# Data_Logger_Shield_V2.net
KiCad netlist of a schematic drawn in Altium Designer
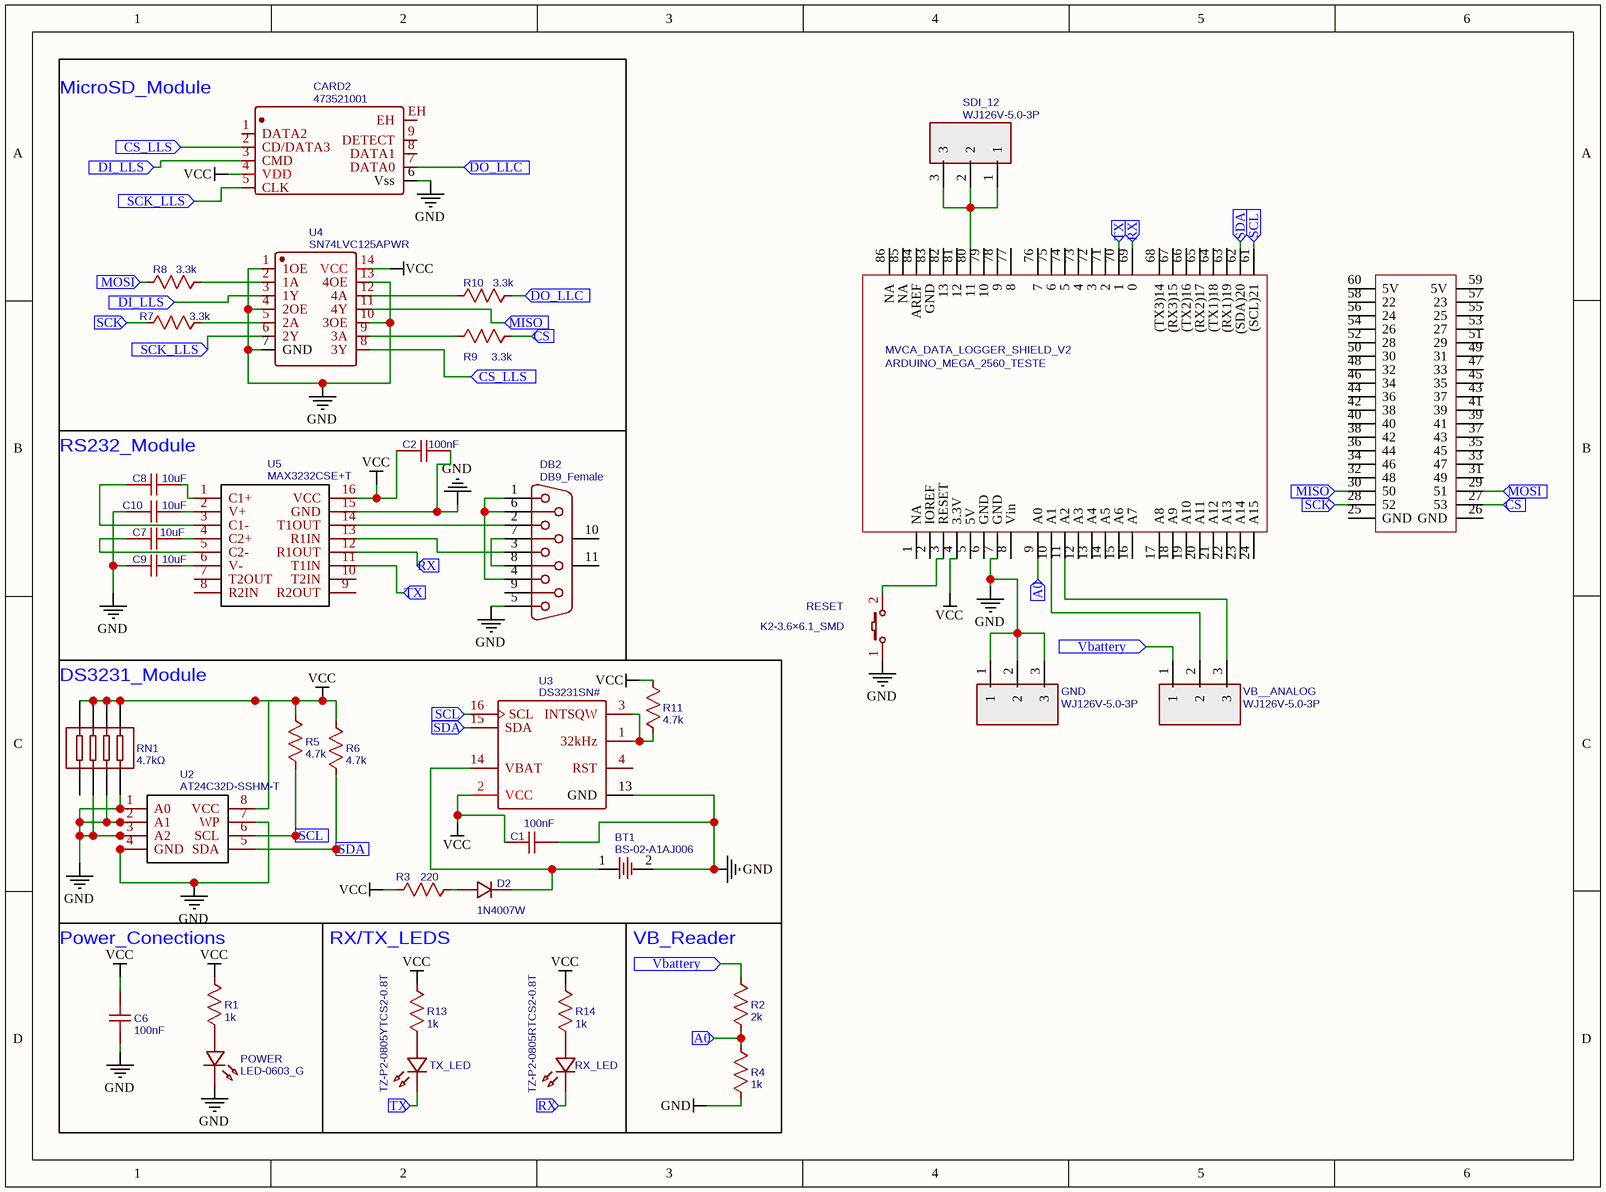
[diagram p0: Data Logger Shield V2.schdoc]

(export (version "E")
  (design (tool "Eeschema 10.0.6"))
  (components
    (comp (ref "BT1")
      (value "BS-02-A1AJ006")
      (fields (field (name "MANUFACTURER") "MYOUNG(美阳)") (field (name "CONTRIBUTOR") "LCSC"))
      (libsource (lib "altium-import") (part "root_0_BS-02-A1AJ006_"))
    )
    (comp (ref "C1")
      (value "100nF")
      (fields (field (name "CONTRIBUTOR") "LCEDA_Lib"))
      (libsource (lib "altium-import") (part "root_2_100nF_"))
    )
    (comp (ref "C2")
      (value "100nF")
      (fields (field (name "CONTRIBUTOR") "LCEDA_Lib"))
      (libsource (lib "altium-import") (part "root_0_100nF_"))
    )
    (comp (ref "C6")
      (value "100nF")
      (fields (field (name "CONTRIBUTOR") "LCEDA_Lib"))
      (libsource (lib "altium-import") (part "root_1_100nF_"))
    )
    (comp (ref "C7")
      (value "10uF")
      (fields (field (name "CONTRIBUTOR") "LCEDA_Lib"))
      (libsource (lib "altium-import") (part "root_0_10uF_"))
    )
    (comp (ref "C8")
      (value "10uF")
      (fields (field (name "CONTRIBUTOR") "LCEDA_Lib"))
      (libsource (lib "altium-import") (part "root_0_10uF_"))
    )
    (comp (ref "C9")
      (value "10uF")
      (fields (field (name "CONTRIBUTOR") "LCEDA_Lib"))
      (libsource (lib "altium-import") (part "root_0_10uF_"))
    )
    (comp (ref "C10")
      (value "10uF")
      (fields (field (name "CONTRIBUTOR") "LCEDA_Lib"))
      (libsource (lib "altium-import") (part "root_0_10uF_"))
    )
    (comp (ref "CARD2")
      (value "473521001")
      (fields (field (name "MANUFACTURER") "MOLEX") (field (name "CONTRIBUTOR") "LCSC"))
      (libsource (lib "altium-import") (part "root_0_473521001_"))
    )
    (comp (ref "D2")
      (value "1N4007W")
      (fields (field (name "MANUFACTURER") "BLUE ROCKET") (field (name "CONTRIBUTOR") "LCEDA_Lib"))
      (libsource (lib "altium-import") (part "root_0_1N4007W_"))
    )
    (comp (ref "DB2")
      (value "DB9_Female")
      (fields (field (name "MANUFACTURER") "Ckmtw(灿科盟)") (field (name "CONTRIBUTOR") "LCEDA_Lib"))
      (libsource (lib "altium-import") (part "root_0_DB9_Female_"))
    )
    (comp (ref "GND")
      (value "WJ126V-5.0-3P")
      (fields (field (name "MANUFACTURER") "KANGNEX(康奈克斯电气)"))
      (libsource (lib "altium-import") (part "root_1_WJ126V-5.0-3P_"))
    )
    (comp (ref "MVCA_DATA_LOGGER_SHIELD_V2")
      (value "ARDUINO_MEGA_2560_TESTE")
      (fields (field (name "MANUFACTURER") "Teste") (field (name "CONTRIBUTOR") "kaiquesuper20"))
      (libsource (lib "altium-import") (part "root_0_ARDUINO_MEGA_2560_TESTE_"))
    )
    (comp (ref "POWER")
      (value "LED-0603_G")
      (fields
        (field (name "MANUFACTURER") "EVERLIGHT(台湾亿光)")
        (field (name "MANUFACTURER PART") "19-217/GHC-YR1S2/3T")
        (field (name "CONTRIBUTOR") "LCEDA_Lib")
      )
      (libsource (lib "altium-import") (part "root_3_LED-0603_G_"))
    )
    (comp (ref "R1")
      (value "1k")
      (fields (field (name "CONTRIBUTOR") "LCEDA_Lib"))
      (libsource (lib "altium-import") (part "root_1_1k_"))
    )
    (comp (ref "R2")
      (value "2k")
      (fields (field (name "CONTRIBUTOR") "LCEDA_Lib"))
      (libsource (lib "altium-import") (part "root_3_2k_"))
    )
    (comp (ref "R3")
      (value "220")
      (fields (field (name "CONTRIBUTOR") "LCEDA_Lib"))
      (libsource (lib "altium-import") (part "root_2_220_"))
    )
    (comp (ref "R4")
      (value "1k")
      (fields (field (name "CONTRIBUTOR") "LCEDA_Lib"))
      (libsource (lib "altium-import") (part "root_3_1k_"))
    )
    (comp (ref "R5")
      (value "4.7k")
      (fields (field (name "CONTRIBUTOR") "LCEDA_Lib"))
      (libsource (lib "altium-import") (part "root_1_4.7k_"))
    )
    (comp (ref "R6")
      (value "4.7k")
      (fields (field (name "CONTRIBUTOR") "LCEDA_Lib"))
      (libsource (lib "altium-import") (part "root_1_4.7k_"))
    )
    (comp (ref "R7")
      (value "3.3k")
      (fields (field (name "CONTRIBUTOR") "LCEDA_Lib"))
      (libsource (lib "altium-import") (part "root_0_3.3k_"))
    )
    (comp (ref "R8")
      (value "3.3k")
      (fields (field (name "CONTRIBUTOR") "LCEDA_Lib"))
      (libsource (lib "altium-import") (part "root_0_3.3k_"))
    )
    (comp (ref "R9")
      (value "3.3k")
      (fields (field (name "CONTRIBUTOR") "LCEDA_Lib"))
      (libsource (lib "altium-import") (part "root_0_3.3k_"))
    )
    (comp (ref "R10")
      (value "3.3k")
      (fields (field (name "CONTRIBUTOR") "LCEDA_Lib"))
      (libsource (lib "altium-import") (part "root_0_3.3k_"))
    )
    (comp (ref "R11")
      (value "4.7k")
      (fields (field (name "CONTRIBUTOR") "LCEDA_Lib"))
      (libsource (lib "altium-import") (part "root_1_4.7k_"))
    )
    (comp (ref "R13")
      (value "1k")
      (fields (field (name "CONTRIBUTOR") "LCEDA_Lib"))
      (libsource (lib "altium-import") (part "root_1_1k_"))
    )
    (comp (ref "R14")
      (value "1k")
      (fields (field (name "CONTRIBUTOR") "LCEDA_Lib"))
      (libsource (lib "altium-import") (part "root_1_1k_"))
    )
    (comp (ref "RESET")
      (value "K2-3.6×6.1_SMD")
      (fields (field (name "MANUFACTURER PART") "K2-1107ST-A4SW-06") (field (name "CONTRIBUTOR") "LCEDA_Lib"))
      (libsource (lib "altium-import") (part "root_1_K2-3.6×6.1_SMD_"))
    )
    (comp (ref "RN1")
      (value "4.7kΩ")
      (fields
        (field (name "MANUFACTURER") "Walsin(华新科)")
        (field (name "MANUFACTURER PART") "WA04X472JTL")
        (field (name "CONTRIBUTOR") "LCSC")
      )
      (libsource (lib "altium-import") (part "root_0_4.7kΩ_"))
    )
    (comp (ref "RX_LED")
      (value "TZ-P2-0805RTCS2-0.8T")
      (fields (field (name "MANUFACTURER") "TUOZHAN(拓展光电)") (field (name "CONTRIBUTOR") "LCSC"))
      (libsource (lib "altium-import") (part "root_1_TZ-P2-0805RTCS2-0.8T_"))
    )
    (comp (ref "SDI_12")
      (value "WJ126V-5.0-3P")
      (fields (field (name "MANUFACTURER") "KANGNEX(康奈克斯电气)"))
      (libsource (lib "altium-import") (part "root_3_WJ126V-5.0-3P_"))
    )
    (comp (ref "TX_LED")
      (value "TZ-P2-0805YTCS2-0.8T")
      (fields (field (name "MANUFACTURER") "TUOZHAN(拓展光电)") (field (name "CONTRIBUTOR") "LCSC"))
      (libsource (lib "altium-import") (part "root_1_TZ-P2-0805YTCS2-0.8T_"))
    )
    (comp (ref "U2")
      (value "AT24C32D-SSHM-T")
      (fields (field (name "MANUFACTURER") "MICROCHIP"))
      (libsource (lib "altium-import") (part "root_0_AT24C32D-SSHM-T_"))
    )
    (comp (ref "U3")
      (value "DS3231SN#")
      (fields
        (field (name "MANUFACTURER") "ADI(亚德诺)/MAXIM(美信)")
        (field (name "MANUFACTURER PART") "DS3231SN#T&R")
        (field (name "SUBPART_NO") "1")
      )
      (libsource (lib "altium-import") (part "root_0_DS3231SN#_"))
    )
    (comp (ref "U4")
      (value "SN74LVC125APWR")
      (fields (field (name "MANUFACTURER") "TI(德州仪器)"))
      (libsource (lib "altium-import") (part "root_0_SN74LVC125APWR_"))
    )
    (comp (ref "U5")
      (value "MAX3232CSE+T")
      (fields (field (name "MANUFACTURER") "ADI(亚德诺)/MAXIM(美信)"))
      (libsource (lib "altium-import") (part "root_0_MAX3232CSE+T_"))
    )
    (comp (ref "VB__ANALOG")
      (value "WJ126V-5.0-3P")
      (fields (field (name "MANUFACTURER") "KANGNEX(康奈克斯电气)"))
      (libsource (lib "altium-import") (part "root_1_WJ126V-5.0-3P_"))
    )
  )
  (nets
    (net (code "1") (name "/A0") (class "Default")
      (node (ref "MVCA_DATA_LOGGER_SHIELD_V2") (pin "9") (pinfunction "A0_9") (pintype "passive"))
      (node (ref "R2") (pin "2") (pinfunction "2_2") (pintype "passive"))
      (node (ref "R4") (pin "1") (pinfunction "1_1") (pintype "passive"))
    )
    (net (code "2") (name "/CS") (class "Default")
      (node (ref "MVCA_DATA_LOGGER_SHIELD_V2") (pin "27") (pinfunction "53_27") (pintype "passive"))
      (node (ref "R9") (pin "2") (pinfunction "2_2") (pintype "passive"))
    )
    (net (code "3") (name "/CS_LLS") (class "Default")
      (node (ref "CARD2") (pin "2") (pinfunction "CD/DATA3_2") (pintype "passive"))
      (node (ref "U4") (pin "8") (pinfunction "3Y_8") (pintype "passive"))
    )
    (net (code "4") (name "/DI_LLS") (class "Default")
      (node (ref "CARD2") (pin "3") (pinfunction "CMD_3") (pintype "passive"))
      (node (ref "U4") (pin "3") (pinfunction "1Y_3") (pintype "passive"))
    )
    (net (code "5") (name "/DO_LLC") (class "Default")
      (node (ref "CARD2") (pin "7") (pinfunction "DATA0_7") (pintype "passive"))
      (node (ref "R10") (pin "2") (pinfunction "2_2") (pintype "passive"))
    )
    (net (code "6") (name "/MISO") (class "Default")
      (node (ref "MVCA_DATA_LOGGER_SHIELD_V2") (pin "30") (pinfunction "50_30") (pintype "passive"))
      (node (ref "U4") (pin "11") (pinfunction "4Y_11") (pintype "passive"))
    )
    (net (code "7") (name "/MOSI") (class "Default")
      (node (ref "MVCA_DATA_LOGGER_SHIELD_V2") (pin "29") (pinfunction "51_29") (pintype "passive"))
      (node (ref "R8") (pin "1") (pinfunction "1_1") (pintype "passive"))
    )
    (net (code "8") (name "/RX") (class "Default")
      (node (ref "MVCA_DATA_LOGGER_SHIELD_V2") (pin "69") (pinfunction "0_69") (pintype "passive"))
      (node (ref "RX_LED") (pin "1") (pinfunction "K_1") (pintype "passive"))
      (node (ref "U5") (pin "12") (pinfunction "R1OUT_12") (pintype "passive"))
    )
    (net (code "9") (name "/SCK") (class "Default")
      (node (ref "MVCA_DATA_LOGGER_SHIELD_V2") (pin "28") (pinfunction "52_28") (pintype "passive"))
      (node (ref "R7") (pin "1") (pinfunction "1_1") (pintype "passive"))
    )
    (net (code "10") (name "/SCK_LLS") (class "Default")
      (node (ref "CARD2") (pin "5") (pinfunction "CLK_5") (pintype "passive"))
      (node (ref "U4") (pin "6") (pinfunction "2Y_6") (pintype "passive"))
    )
    (net (code "11") (name "/SCL") (class "Default")
      (node (ref "MVCA_DATA_LOGGER_SHIELD_V2") (pin "61") (pinfunction "(SCL)21_61") (pintype "passive"))
      (node (ref "R5") (pin "1") (pinfunction "1_1") (pintype "passive"))
      (node (ref "U2") (pin "6") (pinfunction "SCL_6") (pintype "passive"))
      (node (ref "U3") (pin "16") (pinfunction "SCL_16") (pintype "passive"))
    )
    (net (code "12") (name "/SDA") (class "Default")
      (node (ref "MVCA_DATA_LOGGER_SHIELD_V2") (pin "62") (pinfunction "(SDA)20_62") (pintype "passive"))
      (node (ref "R6") (pin "1") (pinfunction "1_1") (pintype "passive"))
      (node (ref "U2") (pin "5") (pinfunction "SDA_5") (pintype "passive"))
      (node (ref "U3") (pin "15") (pinfunction "SDA_15") (pintype "passive"))
    )
    (net (code "13") (name "/TX") (class "Default")
      (node (ref "MVCA_DATA_LOGGER_SHIELD_V2") (pin "70") (pinfunction "1_70") (pintype "passive"))
      (node (ref "TX_LED") (pin "1") (pinfunction "K_1") (pintype "passive"))
      (node (ref "U5") (pin "11") (pinfunction "T1IN_11") (pintype "passive"))
    )
    (net (code "14") (name "/Vbattery") (class "Default")
      (node (ref "R2") (pin "1") (pinfunction "1_1") (pintype "passive"))
      (node (ref "VB__ANALOG") (pin "1") (pinfunction "1_1") (pintype "passive"))
    )
    (net (code "15") (name "GND") (class "Default")
      (node (ref "BT1") (pin "2") (pinfunction "2_2") (pintype "passive"))
      (node (ref "C1") (pin "1") (pinfunction "1_1") (pintype "passive"))
      (node (ref "C10") (pin "1") (pinfunction "1_1") (pintype "passive"))
      (node (ref "C2") (pin "2") (pinfunction "2_2") (pintype "passive"))
      (node (ref "C6") (pin "1") (pinfunction "1_1") (pintype "passive"))
      (node (ref "C9") (pin "1") (pinfunction "1_1") (pintype "passive"))
      (node (ref "CARD2") (pin "6") (pinfunction "Vss_6") (pintype "passive"))
      (node (ref "DB2") (pin "5") (pinfunction "5_5") (pintype "passive"))
      (node (ref "GND") (pin "1") (pinfunction "1_1") (pintype "passive"))
      (node (ref "GND") (pin "2") (pinfunction "2_2") (pintype "passive"))
      (node (ref "GND") (pin "3") (pinfunction "3_3") (pintype "passive"))
      (node (ref "MVCA_DATA_LOGGER_SHIELD_V2") (pin "7") (pinfunction "GND_7") (pintype "passive"))
      (node (ref "POWER") (pin "2") (pinfunction "2_2") (pintype "passive"))
      (node (ref "R4") (pin "2") (pinfunction "2_2") (pintype "passive"))
      (node (ref "RESET") (pin "1") (pinfunction "1_1") (pintype "passive"))
      (node (ref "RN1") (pin "2") (pinfunction "2_2") (pintype "passive"))
      (node (ref "RN1") (pin "3") (pinfunction "3_3") (pintype "passive"))
      (node (ref "RN1") (pin "4") (pinfunction "4_4") (pintype "passive"))
      (node (ref "U2") (pin "1") (pinfunction "A0_1") (pintype "passive"))
      (node (ref "U2") (pin "2") (pinfunction "A1_2") (pintype "passive"))
      (node (ref "U2") (pin "3") (pinfunction "A2_3") (pintype "passive"))
      (node (ref "U2") (pin "4") (pinfunction "GND_4") (pintype "passive"))
      (node (ref "U2") (pin "7") (pinfunction "WP_7") (pintype "passive"))
      (node (ref "U3") (pin "13") (pinfunction "GND_13") (pintype "passive"))
      (node (ref "U4") (pin "1") (pinfunction "1OE_1") (pintype "passive"))
      (node (ref "U4") (pin "10") (pinfunction "3OE_10") (pintype "passive"))
      (node (ref "U4") (pin "13") (pinfunction "4OE_13") (pintype "passive"))
      (node (ref "U4") (pin "4") (pinfunction "2OE_4") (pintype "passive"))
      (node (ref "U4") (pin "7") (pinfunction "GND_7") (pintype "passive"))
      (node (ref "U5") (pin "15") (pinfunction "GND_15") (pintype "passive"))
    )
    (net (code "16") (name "Net-(D2-Pad2)") (class "Default")
      (node (ref "D2") (pin "2") (pinfunction "2_2") (pintype "passive"))
      (node (ref "R3") (pin "1") (pinfunction "1_1") (pintype "passive"))
    )
    (net (code "17") (name "Net-(DB2-Pad1)") (class "Default")
      (node (ref "DB2") (pin "1") (pinfunction "1_1") (pintype "passive"))
      (node (ref "DB2") (pin "4") (pinfunction "4_4") (pintype "passive"))
      (node (ref "DB2") (pin "6") (pinfunction "6_6") (pintype "passive"))
    )
    (net (code "18") (name "Net-(DB2-Pad7)") (class "Default")
      (node (ref "DB2") (pin "7") (pinfunction "7_7") (pintype "passive"))
      (node (ref "DB2") (pin "8") (pinfunction "8_8") (pintype "passive"))
    )
    (net (code "19") (name "Net-(MVCA_DATA_LOGGER_SHIELD_V2-11)") (class "Default")
      (node (ref "MVCA_DATA_LOGGER_SHIELD_V2") (pin "80") (pinfunction "11_80") (pintype "passive"))
      (node (ref "SDI_12") (pin "1") (pinfunction "1_1") (pintype "passive"))
      (node (ref "SDI_12") (pin "2") (pinfunction "2_2") (pintype "passive"))
      (node (ref "SDI_12") (pin "3") (pinfunction "3_3") (pintype "passive"))
    )
    (net (code "20") (name "Net-(MVCA_DATA_LOGGER_SHIELD_V2-A1)") (class "Default")
      (node (ref "MVCA_DATA_LOGGER_SHIELD_V2") (pin "10") (pinfunction "A1_10") (pintype "passive"))
      (node (ref "VB__ANALOG") (pin "2") (pinfunction "2_2") (pintype "passive"))
    )
    (net (code "21") (name "Net-(MVCA_DATA_LOGGER_SHIELD_V2-A2)") (class "Default")
      (node (ref "MVCA_DATA_LOGGER_SHIELD_V2") (pin "11") (pinfunction "A2_11") (pintype "passive"))
      (node (ref "VB__ANALOG") (pin "3") (pinfunction "3_3") (pintype "passive"))
    )
    (net (code "22") (name "Net-(MVCA_DATA_LOGGER_SHIELD_V2-RESET)") (class "Default")
      (node (ref "MVCA_DATA_LOGGER_SHIELD_V2") (pin "3") (pinfunction "RESET_3") (pintype "passive"))
      (node (ref "RESET") (pin "2") (pinfunction "2_2") (pintype "passive"))
    )
    (net (code "23") (name "Net-(POWER-Pad1)") (class "Default")
      (node (ref "POWER") (pin "1") (pinfunction "1_1") (pintype "passive"))
      (node (ref "R1") (pin "1") (pinfunction "1_1") (pintype "passive"))
    )
    (net (code "24") (name "Net-(RX_LED-A)") (class "Default")
      (node (ref "R14") (pin "1") (pinfunction "1_1") (pintype "passive"))
      (node (ref "RX_LED") (pin "2") (pinfunction "A_2") (pintype "passive"))
    )
    (net (code "25") (name "Net-(TX_LED-A)") (class "Default")
      (node (ref "R13") (pin "1") (pinfunction "1_1") (pintype "passive"))
      (node (ref "TX_LED") (pin "2") (pinfunction "A_2") (pintype "passive"))
    )
    (net (code "26") (name "Net-(U3-32kHz)") (class "Default")
      (node (ref "R11") (pin "1") (pinfunction "1_1") (pintype "passive"))
      (node (ref "U3") (pin "1") (pinfunction "32kHz_1") (pintype "passive"))
      (node (ref "U3") (pin "3") (pinfunction "INTSQW_3") (pintype "passive"))
    )
    (net (code "27") (name "Net-(U3-VBAT)") (class "Default")
      (node (ref "BT1") (pin "1") (pinfunction "1_1") (pintype "passive"))
      (node (ref "D2") (pin "1") (pinfunction "1_1") (pintype "passive"))
      (node (ref "U3") (pin "14") (pinfunction "VBAT_14") (pintype "passive"))
    )
    (net (code "28") (name "Net-(U4-1A)") (class "Default")
      (node (ref "R8") (pin "2") (pinfunction "2_2") (pintype "passive"))
      (node (ref "U4") (pin "2") (pinfunction "1A_2") (pintype "passive"))
    )
    (net (code "29") (name "Net-(U4-2A)") (class "Default")
      (node (ref "R7") (pin "2") (pinfunction "2_2") (pintype "passive"))
      (node (ref "U4") (pin "5") (pinfunction "2A_5") (pintype "passive"))
    )
    (net (code "30") (name "Net-(U4-3A)") (class "Default")
      (node (ref "R9") (pin "1") (pinfunction "1_1") (pintype "passive"))
      (node (ref "U4") (pin "9") (pinfunction "3A_9") (pintype "passive"))
    )
    (net (code "31") (name "Net-(U4-4A)") (class "Default")
      (node (ref "R10") (pin "1") (pinfunction "1_1") (pintype "passive"))
      (node (ref "U4") (pin "12") (pinfunction "4A_12") (pintype "passive"))
    )
    (net (code "32") (name "Net-(U5-C1+)") (class "Default")
      (node (ref "C8") (pin "2") (pinfunction "2_2") (pintype "passive"))
      (node (ref "U5") (pin "1") (pinfunction "C1+_1") (pintype "passive"))
    )
    (net (code "33") (name "Net-(U5-C1-)") (class "Default")
      (node (ref "C8") (pin "1") (pinfunction "1_1") (pintype "passive"))
      (node (ref "U5") (pin "3") (pinfunction "C1-_3") (pintype "passive"))
    )
    (net (code "34") (name "Net-(U5-C2+)") (class "Default")
      (node (ref "C7") (pin "2") (pinfunction "2_2") (pintype "passive"))
      (node (ref "U5") (pin "4") (pinfunction "C2+_4") (pintype "passive"))
    )
    (net (code "35") (name "Net-(U5-C2-)") (class "Default")
      (node (ref "C7") (pin "1") (pinfunction "1_1") (pintype "passive"))
      (node (ref "U5") (pin "5") (pinfunction "C2-_5") (pintype "passive"))
    )
    (net (code "36") (name "Net-(U5-R1IN)") (class "Default")
      (node (ref "DB2") (pin "3") (pinfunction "3_3") (pintype "passive"))
      (node (ref "U5") (pin "13") (pinfunction "R1IN_13") (pintype "passive"))
    )
    (net (code "37") (name "Net-(U5-T1OUT)") (class "Default")
      (node (ref "DB2") (pin "2") (pinfunction "2_2") (pintype "passive"))
      (node (ref "U5") (pin "14") (pinfunction "T1OUT_14") (pintype "passive"))
    )
    (net (code "38") (name "Net-(U5-V+)") (class "Default")
      (node (ref "C10") (pin "2") (pinfunction "2_2") (pintype "passive"))
      (node (ref "U5") (pin "2") (pinfunction "V+_2") (pintype "passive"))
    )
    (net (code "39") (name "Net-(U5-V-)") (class "Default")
      (node (ref "C9") (pin "2") (pinfunction "2_2") (pintype "passive"))
      (node (ref "U5") (pin "6") (pinfunction "V-_6") (pintype "passive"))
    )
    (net (code "40") (name "VCC") (class "Default")
      (node (ref "C1") (pin "2") (pinfunction "2_2") (pintype "passive"))
      (node (ref "C2") (pin "1") (pinfunction "1_1") (pintype "passive"))
      (node (ref "C6") (pin "2") (pinfunction "2_2") (pintype "passive"))
      (node (ref "CARD2") (pin "4") (pinfunction "VDD_4") (pintype "passive"))
      (node (ref "MVCA_DATA_LOGGER_SHIELD_V2") (pin "4") (pinfunction "3.3V_4") (pintype "passive"))
      (node (ref "R1") (pin "2") (pinfunction "2_2") (pintype "passive"))
      (node (ref "R11") (pin "2") (pinfunction "2_2") (pintype "passive"))
      (node (ref "R13") (pin "2") (pinfunction "2_2") (pintype "passive"))
      (node (ref "R14") (pin "2") (pinfunction "2_2") (pintype "passive"))
      (node (ref "R3") (pin "2") (pinfunction "2_2") (pintype "passive"))
      (node (ref "R5") (pin "2") (pinfunction "2_2") (pintype "passive"))
      (node (ref "R6") (pin "2") (pinfunction "2_2") (pintype "passive"))
      (node (ref "RN1") (pin "5") (pinfunction "5_5") (pintype "passive"))
      (node (ref "RN1") (pin "6") (pinfunction "6_6") (pintype "passive"))
      (node (ref "RN1") (pin "7") (pinfunction "7_7") (pintype "passive"))
      (node (ref "RN1") (pin "8") (pinfunction "8_8") (pintype "passive"))
      (node (ref "U2") (pin "8") (pinfunction "VCC_8") (pintype "passive"))
      (node (ref "U3") (pin "2") (pinfunction "VCC_2") (pintype "passive"))
      (node (ref "U4") (pin "14") (pinfunction "VCC_14") (pintype "passive"))
      (node (ref "U5") (pin "16") (pinfunction "VCC_16") (pintype "passive"))
    )
    (net (code "41") (name "unconnected-(CARD2-DATA1-Pad8)") (class "Default")
      (node (ref "CARD2") (pin "8") (pinfunction "DATA1_8") (pintype "passive"))
    )
    (net (code "42") (name "unconnected-(CARD2-DATA2-Pad1)") (class "Default")
      (node (ref "CARD2") (pin "1") (pinfunction "DATA2_1") (pintype "passive"))
    )
    (net (code "43") (name "unconnected-(CARD2-DETECT-Pad9)") (class "Default")
      (node (ref "CARD2") (pin "9") (pinfunction "DETECT_9") (pintype "passive"))
    )
    (net (code "44") (name "unconnected-(CARD2-PadEH)") (class "Default")
      (node (ref "CARD2") (pin "EH") (pinfunction "EH_EH") (pintype "passive"))
    )
    (net (code "45") (name "unconnected-(DB2-MH1-Pad10)") (class "Default")
      (node (ref "DB2") (pin "10") (pinfunction "MH1_10") (pintype "passive"))
    )
    (net (code "46") (name "unconnected-(DB2-MH2-Pad11)") (class "Default")
      (node (ref "DB2") (pin "11") (pinfunction "MH2_11") (pintype "passive"))
    )
    (net (code "47") (name "unconnected-(DB2-Pad9)") (class "Default")
      (node (ref "DB2") (pin "9") (pinfunction "9_9") (pintype "passive"))
    )
    (net (code "48") (name "unconnected-(MVCA_DATA_LOGGER_SHIELD_V2-(RX1)19-Pad63)") (class "Default")
      (node (ref "MVCA_DATA_LOGGER_SHIELD_V2") (pin "63") (pinfunction "(RX1)19_63") (pintype "passive"))
    )
    (net (code "49") (name "unconnected-(MVCA_DATA_LOGGER_SHIELD_V2-(RX2)17-Pad65)") (class "Default")
      (node (ref "MVCA_DATA_LOGGER_SHIELD_V2") (pin "65") (pinfunction "(RX2)17_65") (pintype "passive"))
    )
    (net (code "50") (name "unconnected-(MVCA_DATA_LOGGER_SHIELD_V2-(RX3)15-Pad67)") (class "Default")
      (node (ref "MVCA_DATA_LOGGER_SHIELD_V2") (pin "67") (pinfunction "(RX3)15_67") (pintype "passive"))
    )
    (net (code "51") (name "unconnected-(MVCA_DATA_LOGGER_SHIELD_V2-(TX1)18-Pad64)") (class "Default")
      (node (ref "MVCA_DATA_LOGGER_SHIELD_V2") (pin "64") (pinfunction "(TX1)18_64") (pintype "passive"))
    )
    (net (code "52") (name "unconnected-(MVCA_DATA_LOGGER_SHIELD_V2-(TX2)16-Pad66)") (class "Default")
      (node (ref "MVCA_DATA_LOGGER_SHIELD_V2") (pin "66") (pinfunction "(TX2)16_66") (pintype "passive"))
    )
    (net (code "53") (name "unconnected-(MVCA_DATA_LOGGER_SHIELD_V2-(TX3)14-Pad68)") (class "Default")
      (node (ref "MVCA_DATA_LOGGER_SHIELD_V2") (pin "68") (pinfunction "(TX3)14_68") (pintype "passive"))
    )
    (net (code "54") (name "unconnected-(MVCA_DATA_LOGGER_SHIELD_V2-2-Pad71)") (class "Default")
      (node (ref "MVCA_DATA_LOGGER_SHIELD_V2") (pin "71") (pinfunction "2_71") (pintype "passive"))
    )
    (net (code "55") (name "unconnected-(MVCA_DATA_LOGGER_SHIELD_V2-3-Pad72)") (class "Default")
      (node (ref "MVCA_DATA_LOGGER_SHIELD_V2") (pin "72") (pinfunction "3_72") (pintype "passive"))
    )
    (net (code "56") (name "unconnected-(MVCA_DATA_LOGGER_SHIELD_V2-4-Pad73)") (class "Default")
      (node (ref "MVCA_DATA_LOGGER_SHIELD_V2") (pin "73") (pinfunction "4_73") (pintype "passive"))
    )
    (net (code "57") (name "unconnected-(MVCA_DATA_LOGGER_SHIELD_V2-5-Pad74)") (class "Default")
      (node (ref "MVCA_DATA_LOGGER_SHIELD_V2") (pin "74") (pinfunction "5_74") (pintype "passive"))
    )
    (net (code "58") (name "unconnected-(MVCA_DATA_LOGGER_SHIELD_V2-5V-Pad5)") (class "Default")
      (node (ref "MVCA_DATA_LOGGER_SHIELD_V2") (pin "5") (pinfunction "5V_5") (pintype "passive"))
    )
    (net (code "59") (name "unconnected-(MVCA_DATA_LOGGER_SHIELD_V2-5V-Pad59)") (class "Default")
      (node (ref "MVCA_DATA_LOGGER_SHIELD_V2") (pin "59") (pinfunction "5V_59") (pintype "passive"))
    )
    (net (code "60") (name "unconnected-(MVCA_DATA_LOGGER_SHIELD_V2-5V-Pad60)") (class "Default")
      (node (ref "MVCA_DATA_LOGGER_SHIELD_V2") (pin "60") (pinfunction "5V_60") (pintype "passive"))
    )
    (net (code "61") (name "unconnected-(MVCA_DATA_LOGGER_SHIELD_V2-6-Pad75)") (class "Default")
      (node (ref "MVCA_DATA_LOGGER_SHIELD_V2") (pin "75") (pinfunction "6_75") (pintype "passive"))
    )
    (net (code "62") (name "unconnected-(MVCA_DATA_LOGGER_SHIELD_V2-7-Pad76)") (class "Default")
      (node (ref "MVCA_DATA_LOGGER_SHIELD_V2") (pin "76") (pinfunction "7_76") (pintype "passive"))
    )
    (net (code "63") (name "unconnected-(MVCA_DATA_LOGGER_SHIELD_V2-8-Pad77)") (class "Default")
      (node (ref "MVCA_DATA_LOGGER_SHIELD_V2") (pin "77") (pinfunction "8_77") (pintype "passive"))
    )
    (net (code "64") (name "unconnected-(MVCA_DATA_LOGGER_SHIELD_V2-9-Pad78)") (class "Default")
      (node (ref "MVCA_DATA_LOGGER_SHIELD_V2") (pin "78") (pinfunction "9_78") (pintype "passive"))
    )
    (net (code "65") (name "unconnected-(MVCA_DATA_LOGGER_SHIELD_V2-10-Pad79)") (class "Default")
      (node (ref "MVCA_DATA_LOGGER_SHIELD_V2") (pin "79") (pinfunction "10_79") (pintype "passive"))
    )
    (net (code "66") (name "unconnected-(MVCA_DATA_LOGGER_SHIELD_V2-12-Pad81)") (class "Default")
      (node (ref "MVCA_DATA_LOGGER_SHIELD_V2") (pin "81") (pinfunction "12_81") (pintype "passive"))
    )
    (net (code "67") (name "unconnected-(MVCA_DATA_LOGGER_SHIELD_V2-13-Pad82)") (class "Default")
      (node (ref "MVCA_DATA_LOGGER_SHIELD_V2") (pin "82") (pinfunction "13_82") (pintype "passive"))
    )
    (net (code "68") (name "unconnected-(MVCA_DATA_LOGGER_SHIELD_V2-22-Pad58)") (class "Default")
      (node (ref "MVCA_DATA_LOGGER_SHIELD_V2") (pin "58") (pinfunction "22_58") (pintype "passive"))
    )
    (net (code "69") (name "unconnected-(MVCA_DATA_LOGGER_SHIELD_V2-23-Pad57)") (class "Default")
      (node (ref "MVCA_DATA_LOGGER_SHIELD_V2") (pin "57") (pinfunction "23_57") (pintype "passive"))
    )
    (net (code "70") (name "unconnected-(MVCA_DATA_LOGGER_SHIELD_V2-24-Pad56)") (class "Default")
      (node (ref "MVCA_DATA_LOGGER_SHIELD_V2") (pin "56") (pinfunction "24_56") (pintype "passive"))
    )
    (net (code "71") (name "unconnected-(MVCA_DATA_LOGGER_SHIELD_V2-25-Pad55)") (class "Default")
      (node (ref "MVCA_DATA_LOGGER_SHIELD_V2") (pin "55") (pinfunction "25_55") (pintype "passive"))
    )
    (net (code "72") (name "unconnected-(MVCA_DATA_LOGGER_SHIELD_V2-26-Pad54)") (class "Default")
      (node (ref "MVCA_DATA_LOGGER_SHIELD_V2") (pin "54") (pinfunction "26_54") (pintype "passive"))
    )
    (net (code "73") (name "unconnected-(MVCA_DATA_LOGGER_SHIELD_V2-27-Pad53)") (class "Default")
      (node (ref "MVCA_DATA_LOGGER_SHIELD_V2") (pin "53") (pinfunction "27_53") (pintype "passive"))
    )
    (net (code "74") (name "unconnected-(MVCA_DATA_LOGGER_SHIELD_V2-28-Pad52)") (class "Default")
      (node (ref "MVCA_DATA_LOGGER_SHIELD_V2") (pin "52") (pinfunction "28_52") (pintype "passive"))
    )
    (net (code "75") (name "unconnected-(MVCA_DATA_LOGGER_SHIELD_V2-29-Pad51)") (class "Default")
      (node (ref "MVCA_DATA_LOGGER_SHIELD_V2") (pin "51") (pinfunction "29_51") (pintype "passive"))
    )
    (net (code "76") (name "unconnected-(MVCA_DATA_LOGGER_SHIELD_V2-30-Pad50)") (class "Default")
      (node (ref "MVCA_DATA_LOGGER_SHIELD_V2") (pin "50") (pinfunction "30_50") (pintype "passive"))
    )
    (net (code "77") (name "unconnected-(MVCA_DATA_LOGGER_SHIELD_V2-31-Pad49)") (class "Default")
      (node (ref "MVCA_DATA_LOGGER_SHIELD_V2") (pin "49") (pinfunction "31_49") (pintype "passive"))
    )
    (net (code "78") (name "unconnected-(MVCA_DATA_LOGGER_SHIELD_V2-32-Pad48)") (class "Default")
      (node (ref "MVCA_DATA_LOGGER_SHIELD_V2") (pin "48") (pinfunction "32_48") (pintype "passive"))
    )
    (net (code "79") (name "unconnected-(MVCA_DATA_LOGGER_SHIELD_V2-33-Pad47)") (class "Default")
      (node (ref "MVCA_DATA_LOGGER_SHIELD_V2") (pin "47") (pinfunction "33_47") (pintype "passive"))
    )
    (net (code "80") (name "unconnected-(MVCA_DATA_LOGGER_SHIELD_V2-34-Pad46)") (class "Default")
      (node (ref "MVCA_DATA_LOGGER_SHIELD_V2") (pin "46") (pinfunction "34_46") (pintype "passive"))
    )
    (net (code "81") (name "unconnected-(MVCA_DATA_LOGGER_SHIELD_V2-35-Pad45)") (class "Default")
      (node (ref "MVCA_DATA_LOGGER_SHIELD_V2") (pin "45") (pinfunction "35_45") (pintype "passive"))
    )
    (net (code "82") (name "unconnected-(MVCA_DATA_LOGGER_SHIELD_V2-36-Pad44)") (class "Default")
      (node (ref "MVCA_DATA_LOGGER_SHIELD_V2") (pin "44") (pinfunction "36_44") (pintype "passive"))
    )
    (net (code "83") (name "unconnected-(MVCA_DATA_LOGGER_SHIELD_V2-37-Pad43)") (class "Default")
      (node (ref "MVCA_DATA_LOGGER_SHIELD_V2") (pin "43") (pinfunction "37_43") (pintype "passive"))
    )
    (net (code "84") (name "unconnected-(MVCA_DATA_LOGGER_SHIELD_V2-38-Pad42)") (class "Default")
      (node (ref "MVCA_DATA_LOGGER_SHIELD_V2") (pin "42") (pinfunction "38_42") (pintype "passive"))
    )
    (net (code "85") (name "unconnected-(MVCA_DATA_LOGGER_SHIELD_V2-39-Pad41)") (class "Default")
      (node (ref "MVCA_DATA_LOGGER_SHIELD_V2") (pin "41") (pinfunction "39_41") (pintype "passive"))
    )
    (net (code "86") (name "unconnected-(MVCA_DATA_LOGGER_SHIELD_V2-41-Pad39)") (class "Default")
      (node (ref "MVCA_DATA_LOGGER_SHIELD_V2") (pin "39") (pinfunction "41_39") (pintype "passive"))
    )
    (net (code "87") (name "unconnected-(MVCA_DATA_LOGGER_SHIELD_V2-42-Pad38)") (class "Default")
      (node (ref "MVCA_DATA_LOGGER_SHIELD_V2") (pin "38") (pinfunction "42_38") (pintype "passive"))
    )
    (net (code "88") (name "unconnected-(MVCA_DATA_LOGGER_SHIELD_V2-43-Pad37)") (class "Default")
      (node (ref "MVCA_DATA_LOGGER_SHIELD_V2") (pin "37") (pinfunction "43_37") (pintype "passive"))
    )
    (net (code "89") (name "unconnected-(MVCA_DATA_LOGGER_SHIELD_V2-44-Pad36)") (class "Default")
      (node (ref "MVCA_DATA_LOGGER_SHIELD_V2") (pin "36") (pinfunction "44_36") (pintype "passive"))
    )
    (net (code "90") (name "unconnected-(MVCA_DATA_LOGGER_SHIELD_V2-45-Pad35)") (class "Default")
      (node (ref "MVCA_DATA_LOGGER_SHIELD_V2") (pin "35") (pinfunction "45_35") (pintype "passive"))
    )
    (net (code "91") (name "unconnected-(MVCA_DATA_LOGGER_SHIELD_V2-46-Pad34)") (class "Default")
      (node (ref "MVCA_DATA_LOGGER_SHIELD_V2") (pin "34") (pinfunction "46_34") (pintype "passive"))
    )
    (net (code "92") (name "unconnected-(MVCA_DATA_LOGGER_SHIELD_V2-47-Pad33)") (class "Default")
      (node (ref "MVCA_DATA_LOGGER_SHIELD_V2") (pin "33") (pinfunction "47_33") (pintype "passive"))
    )
    (net (code "93") (name "unconnected-(MVCA_DATA_LOGGER_SHIELD_V2-48-Pad32)") (class "Default")
      (node (ref "MVCA_DATA_LOGGER_SHIELD_V2") (pin "32") (pinfunction "48_32") (pintype "passive"))
    )
    (net (code "94") (name "unconnected-(MVCA_DATA_LOGGER_SHIELD_V2-49-Pad31)") (class "Default")
      (node (ref "MVCA_DATA_LOGGER_SHIELD_V2") (pin "31") (pinfunction "49_31") (pintype "passive"))
    )
    (net (code "95") (name "unconnected-(MVCA_DATA_LOGGER_SHIELD_V2-A3-Pad12)") (class "Default")
      (node (ref "MVCA_DATA_LOGGER_SHIELD_V2") (pin "12") (pinfunction "A3_12") (pintype "passive"))
    )
    (net (code "96") (name "unconnected-(MVCA_DATA_LOGGER_SHIELD_V2-A4-Pad13)") (class "Default")
      (node (ref "MVCA_DATA_LOGGER_SHIELD_V2") (pin "13") (pinfunction "A4_13") (pintype "passive"))
    )
    (net (code "97") (name "unconnected-(MVCA_DATA_LOGGER_SHIELD_V2-A5-Pad14)") (class "Default")
      (node (ref "MVCA_DATA_LOGGER_SHIELD_V2") (pin "14") (pinfunction "A5_14") (pintype "passive"))
    )
    (net (code "98") (name "unconnected-(MVCA_DATA_LOGGER_SHIELD_V2-A6-Pad15)") (class "Default")
      (node (ref "MVCA_DATA_LOGGER_SHIELD_V2") (pin "15") (pinfunction "A6_15") (pintype "passive"))
    )
    (net (code "99") (name "unconnected-(MVCA_DATA_LOGGER_SHIELD_V2-A7-Pad16)") (class "Default")
      (node (ref "MVCA_DATA_LOGGER_SHIELD_V2") (pin "16") (pinfunction "A7_16") (pintype "passive"))
    )
    (net (code "100") (name "unconnected-(MVCA_DATA_LOGGER_SHIELD_V2-A8-Pad17)") (class "Default")
      (node (ref "MVCA_DATA_LOGGER_SHIELD_V2") (pin "17") (pinfunction "A8_17") (pintype "passive"))
    )
    (net (code "101") (name "unconnected-(MVCA_DATA_LOGGER_SHIELD_V2-A9-Pad18)") (class "Default")
      (node (ref "MVCA_DATA_LOGGER_SHIELD_V2") (pin "18") (pinfunction "A9_18") (pintype "passive"))
    )
    (net (code "102") (name "unconnected-(MVCA_DATA_LOGGER_SHIELD_V2-A10-Pad19)") (class "Default")
      (node (ref "MVCA_DATA_LOGGER_SHIELD_V2") (pin "19") (pinfunction "A10_19") (pintype "passive"))
    )
    (net (code "103") (name "unconnected-(MVCA_DATA_LOGGER_SHIELD_V2-A11-Pad20)") (class "Default")
      (node (ref "MVCA_DATA_LOGGER_SHIELD_V2") (pin "20") (pinfunction "A11_20") (pintype "passive"))
    )
    (net (code "104") (name "unconnected-(MVCA_DATA_LOGGER_SHIELD_V2-A12-Pad21)") (class "Default")
      (node (ref "MVCA_DATA_LOGGER_SHIELD_V2") (pin "21") (pinfunction "A12_21") (pintype "passive"))
    )
    (net (code "105") (name "unconnected-(MVCA_DATA_LOGGER_SHIELD_V2-A13-Pad22)") (class "Default")
      (node (ref "MVCA_DATA_LOGGER_SHIELD_V2") (pin "22") (pinfunction "A13_22") (pintype "passive"))
    )
    (net (code "106") (name "unconnected-(MVCA_DATA_LOGGER_SHIELD_V2-A14-Pad23)") (class "Default")
      (node (ref "MVCA_DATA_LOGGER_SHIELD_V2") (pin "23") (pinfunction "A14_23") (pintype "passive"))
    )
    (net (code "107") (name "unconnected-(MVCA_DATA_LOGGER_SHIELD_V2-A15-Pad24)") (class "Default")
      (node (ref "MVCA_DATA_LOGGER_SHIELD_V2") (pin "24") (pinfunction "A15_24") (pintype "passive"))
    )
    (net (code "108") (name "unconnected-(MVCA_DATA_LOGGER_SHIELD_V2-AREF-Pad84)") (class "Default")
      (node (ref "MVCA_DATA_LOGGER_SHIELD_V2") (pin "84") (pinfunction "AREF_84") (pintype "passive"))
    )
    (net (code "109") (name "unconnected-(MVCA_DATA_LOGGER_SHIELD_V2-GND-Pad6)") (class "Default")
      (node (ref "MVCA_DATA_LOGGER_SHIELD_V2") (pin "6") (pinfunction "GND_6") (pintype "passive"))
    )
    (net (code "110") (name "unconnected-(MVCA_DATA_LOGGER_SHIELD_V2-GND-Pad25)") (class "Default")
      (node (ref "MVCA_DATA_LOGGER_SHIELD_V2") (pin "25") (pinfunction "GND_25") (pintype "passive"))
    )
    (net (code "111") (name "unconnected-(MVCA_DATA_LOGGER_SHIELD_V2-GND-Pad26)") (class "Default")
      (node (ref "MVCA_DATA_LOGGER_SHIELD_V2") (pin "26") (pinfunction "GND_26") (pintype "passive"))
    )
    (net (code "112") (name "unconnected-(MVCA_DATA_LOGGER_SHIELD_V2-GND-Pad83)") (class "Default")
      (node (ref "MVCA_DATA_LOGGER_SHIELD_V2") (pin "83") (pinfunction "GND_83") (pintype "passive"))
    )
    (net (code "113") (name "unconnected-(MVCA_DATA_LOGGER_SHIELD_V2-IOREF-Pad2)") (class "Default")
      (node (ref "MVCA_DATA_LOGGER_SHIELD_V2") (pin "2") (pinfunction "IOREF_2") (pintype "passive"))
    )
    (net (code "114") (name "unconnected-(MVCA_DATA_LOGGER_SHIELD_V2-NA-Pad1)") (class "Default")
      (node (ref "MVCA_DATA_LOGGER_SHIELD_V2") (pin "1") (pinfunction "NA_1") (pintype "passive"))
    )
    (net (code "115") (name "unconnected-(MVCA_DATA_LOGGER_SHIELD_V2-NA-Pad85)") (class "Default")
      (node (ref "MVCA_DATA_LOGGER_SHIELD_V2") (pin "85") (pinfunction "NA_85") (pintype "passive"))
    )
    (net (code "116") (name "unconnected-(MVCA_DATA_LOGGER_SHIELD_V2-NA-Pad86)") (class "Default")
      (node (ref "MVCA_DATA_LOGGER_SHIELD_V2") (pin "86") (pinfunction "NA_86") (pintype "passive"))
    )
    (net (code "117") (name "unconnected-(MVCA_DATA_LOGGER_SHIELD_V2-Pad40)") (class "Default")
      (node (ref "MVCA_DATA_LOGGER_SHIELD_V2") (pin "40") (pinfunction "40_40") (pintype "passive"))
    )
    (net (code "118") (name "unconnected-(MVCA_DATA_LOGGER_SHIELD_V2-Vin-Pad8)") (class "Default")
      (node (ref "MVCA_DATA_LOGGER_SHIELD_V2") (pin "8") (pinfunction "Vin_8") (pintype "passive"))
    )
    (net (code "119") (name "unconnected-(RN1-Pad1)") (class "Default")
      (node (ref "RN1") (pin "1") (pinfunction "1_1") (pintype "passive"))
    )
    (net (code "120") (name "unconnected-(U3-RST-Pad4)") (class "Default")
      (node (ref "U3") (pin "4") (pinfunction "RST_4") (pintype "passive"))
    )
    (net (code "121") (name "unconnected-(U5-R2IN-Pad8)") (class "Default")
      (node (ref "U5") (pin "8") (pinfunction "R2IN_8") (pintype "passive"))
    )
    (net (code "122") (name "unconnected-(U5-R2OUT-Pad9)") (class "Default")
      (node (ref "U5") (pin "9") (pinfunction "R2OUT_9") (pintype "passive"))
    )
    (net (code "123") (name "unconnected-(U5-T2IN-Pad10)") (class "Default")
      (node (ref "U5") (pin "10") (pinfunction "T2IN_10") (pintype "passive"))
    )
    (net (code "124") (name "unconnected-(U5-T2OUT-Pad7)") (class "Default")
      (node (ref "U5") (pin "7") (pinfunction "T2OUT_7") (pintype "passive"))
    )
  )
)
